# NSE2022_IMGPS_ver0.net
KiCad netlist of a schematic drawn in EAGLE
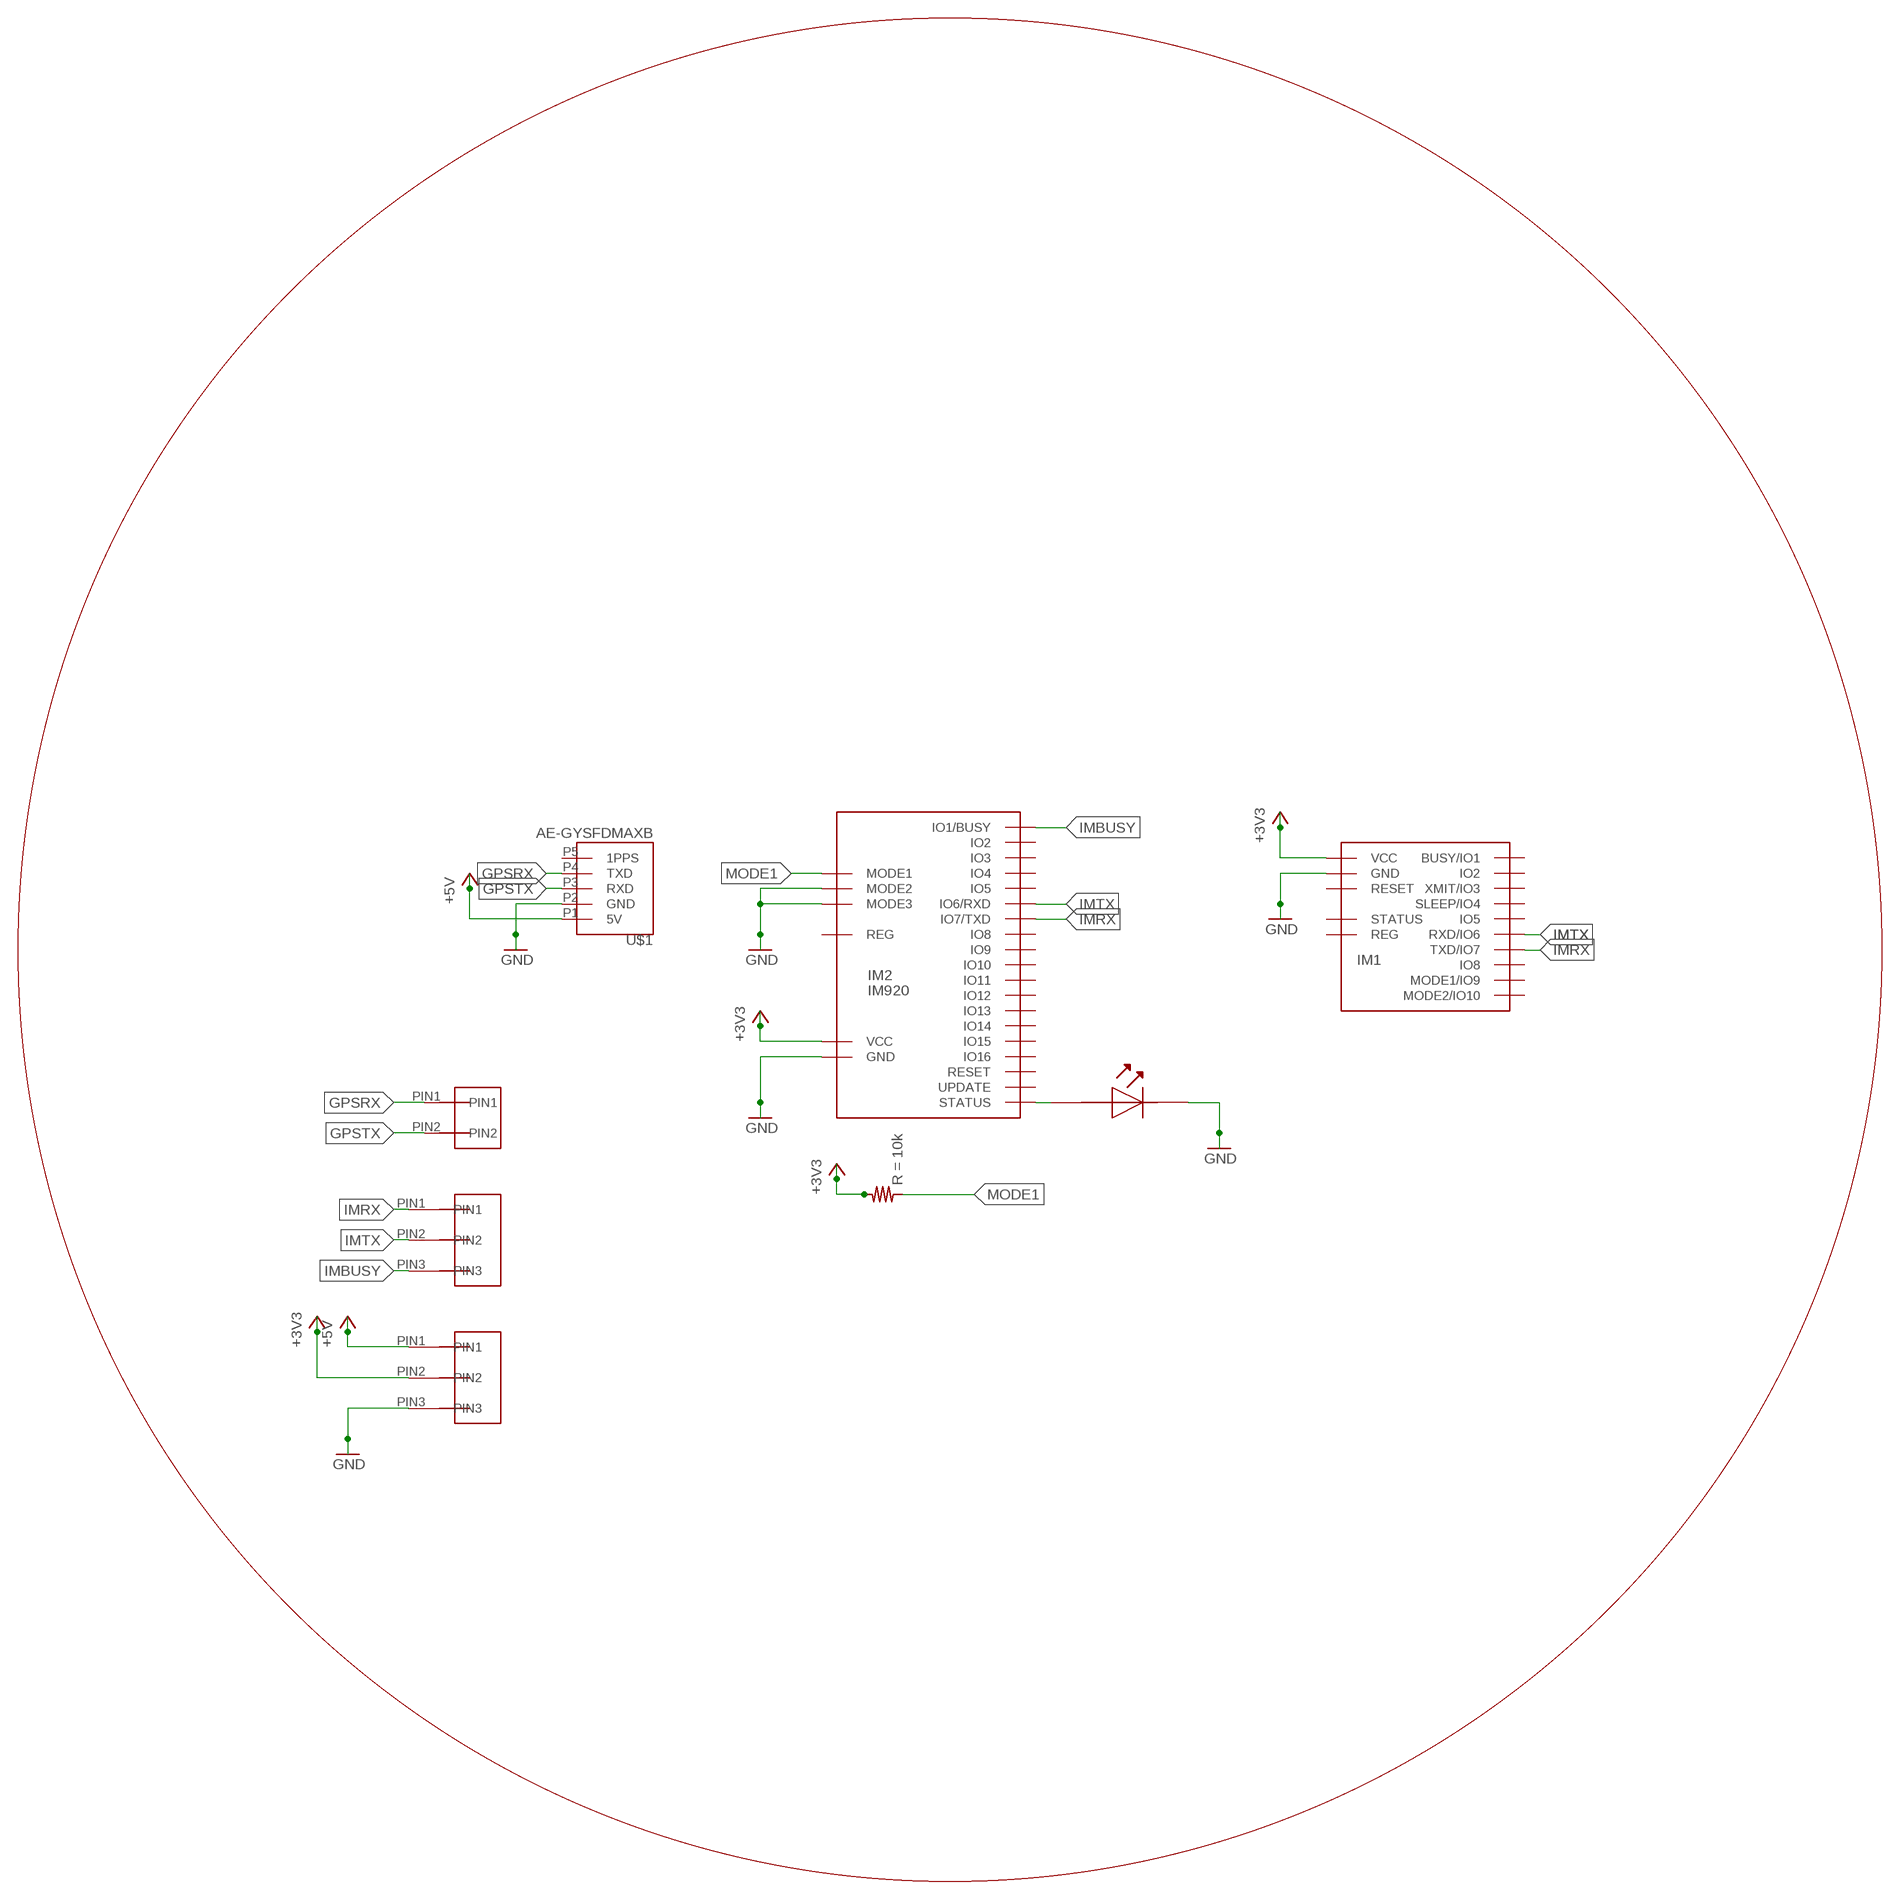
[diagram p0: schematic, sheet 1]

(export (version "E")
  (design (tool "Eeschema 10.0.6"))
  (components
    (comp (ref "IM1")
      (value "IM920C")
      (footprint "eagle-import:IM920C")
      (libsource (lib "eagle-import") (part "IM920C"))
    )
    (comp (ref "IM2")
      (value "IM920")
      (footprint "eagle-import:IM920")
      (libsource (lib "eagle-import") (part "IM920"))
    )
    (comp (ref "R4")
      (value "RESISTER")
      (footprint "eagle-import:REGISTER")
      (fields (field (name "R") "10k"))
      (libsource (lib "eagle-import") (part "RESISTER"))
    )
    (comp (ref "U$1")
      (value "AE-GYSFDMAXB")
      (footprint "eagle-import:AE-GYSFDMAXB")
      (libsource (lib "eagle-import") (part "AE-GYSFDMAXB"))
    )
    (comp (ref "U$33")
      (value "2PIN")
      (footprint "eagle-import:2PIN")
      (libsource (lib "eagle-import") (part "2PIN"))
    )
    (comp (ref "U$47")
      (value "3PIN")
      (footprint "eagle-import:3PIN")
      (libsource (lib "eagle-import") (part "3PIN"))
    )
    (comp (ref "U$48")
      (value "3PIN")
      (footprint "eagle-import:3PIN")
      (libsource (lib "eagle-import") (part "3PIN"))
    )
    (comp (ref "U$54")
      (value "LED")
      (footprint "eagle-import:LED")
      (libsource (lib "eagle-import") (part "LED"))
    )
  )
  (nets
    (net (code "1") (name "+3V3") (class "Default")
      (node (ref "IM1") (pin "$P17") (pinfunction "VCC_$P17") (pintype "bidirectional"))
      (node (ref "IM2") (pin "IO23") (pinfunction "VCC_IO23") (pintype "bidirectional"))
      (node (ref "R4") (pin "B") (pinfunction "B_B") (pintype "bidirectional"))
      (node (ref "U$48") (pin "PIN2") (pinfunction "PIN2_PIN2") (pintype "bidirectional"))
    )
    (net (code "2") (name "+5V") (class "Default")
      (node (ref "U$1") (pin "P1") (pinfunction "5V_P1") (pintype "bidirectional"))
      (node (ref "U$48") (pin "PIN1") (pinfunction "PIN1_PIN1") (pintype "bidirectional"))
    )
    (net (code "3") (name "GND") (class "Default")
      (node (ref "IM1") (pin "$P18") (pinfunction "GND_$P18") (pintype "bidirectional"))
      (node (ref "IM2") (pin "IO18") (pinfunction "MODE2_IO18") (pintype "bidirectional"))
      (node (ref "IM2") (pin "IO19") (pinfunction "MODE3_IO19") (pintype "bidirectional"))
      (node (ref "IM2") (pin "IO24") (pinfunction "GND_IO24") (pintype "bidirectional"))
      (node (ref "U$1") (pin "P2") (pinfunction "GND_P2") (pintype "bidirectional"))
      (node (ref "U$48") (pin "PIN3") (pinfunction "PIN3_PIN3") (pintype "bidirectional"))
      (node (ref "U$54") (pin "PLUS") (pinfunction "OUT_PLUS") (pintype "bidirectional"))
    )
    (net (code "4") (name "GPSRX") (class "Default")
      (node (ref "U$1") (pin "P4") (pinfunction "TXD_P4") (pintype "bidirectional"))
      (node (ref "U$33") (pin "PIN1") (pinfunction "PIN1_PIN1") (pintype "bidirectional"))
    )
    (net (code "5") (name "GPSTX") (class "Default")
      (node (ref "U$1") (pin "P3") (pinfunction "RXD_P3") (pintype "bidirectional"))
      (node (ref "U$33") (pin "PIN2") (pinfunction "PIN2_PIN2") (pintype "bidirectional"))
    )
    (net (code "6") (name "IMBUSY") (class "Default")
      (node (ref "IM2") (pin "IO1") (pinfunction "IO1/BUSY_IO1") (pintype "bidirectional"))
      (node (ref "U$47") (pin "PIN3") (pinfunction "PIN3_PIN3") (pintype "bidirectional"))
    )
    (net (code "7") (name "IMRX") (class "Default")
      (node (ref "IM1") (pin "$P7") (pinfunction "TXD/IO7_$P7") (pintype "bidirectional"))
      (node (ref "IM2") (pin "IO7") (pinfunction "IO7/TXD_IO7") (pintype "bidirectional"))
      (node (ref "U$47") (pin "PIN1") (pinfunction "PIN1_PIN1") (pintype "bidirectional"))
    )
    (net (code "8") (name "IMTX") (class "Default")
      (node (ref "IM1") (pin "$P6") (pinfunction "RXD/IO6_$P6") (pintype "bidirectional"))
      (node (ref "IM2") (pin "IO6") (pinfunction "IO6/RXD_IO6") (pintype "bidirectional"))
      (node (ref "U$47") (pin "PIN2") (pinfunction "PIN2_PIN2") (pintype "bidirectional"))
    )
    (net (code "9") (name "MODE1") (class "Default")
      (node (ref "IM2") (pin "IO17") (pinfunction "MODE1_IO17") (pintype "bidirectional"))
      (node (ref "R4") (pin "A") (pinfunction "A_A") (pintype "bidirectional"))
    )
    (net (code "10") (name "Net-(IM2-STATUS)") (class "Default")
      (node (ref "IM2") (pin "IO21") (pinfunction "STATUS_IO21") (pintype "bidirectional"))
      (node (ref "U$54") (pin "MINUS") (pinfunction "IN_MINUS") (pintype "bidirectional"))
    )
    (net (code "11") (name "unconnected-(IM1-BUSY{slash}IO1-Pad$P1)") (class "Default")
      (node (ref "IM1") (pin "$P1") (pinfunction "BUSY/IO1_$P1") (pintype "bidirectional"))
    )
    (net (code "12") (name "unconnected-(IM1-IO2-Pad$P2)") (class "Default")
      (node (ref "IM1") (pin "$P2") (pinfunction "IO2_$P2") (pintype "bidirectional"))
    )
    (net (code "13") (name "unconnected-(IM1-IO5-Pad$P5)") (class "Default")
      (node (ref "IM1") (pin "$P5") (pinfunction "IO5_$P5") (pintype "bidirectional"))
    )
    (net (code "14") (name "unconnected-(IM1-IO8-Pad$P8)") (class "Default")
      (node (ref "IM1") (pin "$P8") (pinfunction "IO8_$P8") (pintype "bidirectional"))
    )
    (net (code "15") (name "unconnected-(IM1-MODE1{slash}IO9-Pad$P9)") (class "Default")
      (node (ref "IM1") (pin "$P9") (pinfunction "MODE1/IO9_$P9") (pintype "bidirectional"))
    )
    (net (code "16") (name "unconnected-(IM1-MODE2{slash}IO10-Pad$P10)") (class "Default")
      (node (ref "IM1") (pin "$P10") (pinfunction "MODE2/IO10_$P10") (pintype "bidirectional"))
    )
    (net (code "17") (name "unconnected-(IM1-REG-Pad$P16)") (class "Default")
      (node (ref "IM1") (pin "$P16") (pinfunction "REG_$P16") (pintype "bidirectional"))
    )
    (net (code "18") (name "unconnected-(IM1-RESET-Pad$P19)") (class "Default")
      (node (ref "IM1") (pin "$P19") (pinfunction "RESET_$P19") (pintype "bidirectional"))
    )
    (net (code "19") (name "unconnected-(IM1-SLEEP{slash}IO4-Pad$P4)") (class "Default")
      (node (ref "IM1") (pin "$P4") (pinfunction "SLEEP/IO4_$P4") (pintype "bidirectional"))
    )
    (net (code "20") (name "unconnected-(IM1-STATUS-Pad$P15)") (class "Default")
      (node (ref "IM1") (pin "$P15") (pinfunction "STATUS_$P15") (pintype "bidirectional"))
    )
    (net (code "21") (name "unconnected-(IM1-XMIT{slash}IO3-Pad$P3)") (class "Default")
      (node (ref "IM1") (pin "$P3") (pinfunction "XMIT/IO3_$P3") (pintype "bidirectional"))
    )
    (net (code "22") (name "unconnected-(IM2-PadIO2)") (class "Default")
      (node (ref "IM2") (pin "IO2") (pinfunction "IO2_IO2") (pintype "bidirectional"))
    )
    (net (code "23") (name "unconnected-(IM2-PadIO3)") (class "Default")
      (node (ref "IM2") (pin "IO3") (pinfunction "IO3_IO3") (pintype "bidirectional"))
    )
    (net (code "24") (name "unconnected-(IM2-PadIO4)") (class "Default")
      (node (ref "IM2") (pin "IO4") (pinfunction "IO4_IO4") (pintype "bidirectional"))
    )
    (net (code "25") (name "unconnected-(IM2-PadIO5)") (class "Default")
      (node (ref "IM2") (pin "IO5") (pinfunction "IO5_IO5") (pintype "bidirectional"))
    )
    (net (code "26") (name "unconnected-(IM2-PadIO8)") (class "Default")
      (node (ref "IM2") (pin "IO8") (pinfunction "IO8_IO8") (pintype "bidirectional"))
    )
    (net (code "27") (name "unconnected-(IM2-PadIO9)") (class "Default")
      (node (ref "IM2") (pin "IO9") (pinfunction "IO9_IO9") (pintype "bidirectional"))
    )
    (net (code "28") (name "unconnected-(IM2-PadIO10)") (class "Default")
      (node (ref "IM2") (pin "IO10") (pinfunction "IO10_IO10") (pintype "bidirectional"))
    )
    (net (code "29") (name "unconnected-(IM2-PadIO11)") (class "Default")
      (node (ref "IM2") (pin "IO11") (pinfunction "IO11_IO11") (pintype "bidirectional"))
    )
    (net (code "30") (name "unconnected-(IM2-PadIO12)") (class "Default")
      (node (ref "IM2") (pin "IO12") (pinfunction "IO12_IO12") (pintype "bidirectional"))
    )
    (net (code "31") (name "unconnected-(IM2-PadIO13)") (class "Default")
      (node (ref "IM2") (pin "IO13") (pinfunction "IO13_IO13") (pintype "bidirectional"))
    )
    (net (code "32") (name "unconnected-(IM2-PadIO14)") (class "Default")
      (node (ref "IM2") (pin "IO14") (pinfunction "IO14_IO14") (pintype "bidirectional"))
    )
    (net (code "33") (name "unconnected-(IM2-PadIO15)") (class "Default")
      (node (ref "IM2") (pin "IO15") (pinfunction "IO15_IO15") (pintype "bidirectional"))
    )
    (net (code "34") (name "unconnected-(IM2-PadIO16)") (class "Default")
      (node (ref "IM2") (pin "IO16") (pinfunction "IO16_IO16") (pintype "bidirectional"))
    )
    (net (code "35") (name "unconnected-(IM2-REG-PadIO22)") (class "Default")
      (node (ref "IM2") (pin "IO22") (pinfunction "REG_IO22") (pintype "bidirectional"))
    )
    (net (code "36") (name "unconnected-(IM2-RESET-PadIO25)") (class "Default")
      (node (ref "IM2") (pin "IO25") (pinfunction "RESET_IO25") (pintype "bidirectional"))
    )
    (net (code "37") (name "unconnected-(IM2-UPDATE-PadIO20)") (class "Default")
      (node (ref "IM2") (pin "IO20") (pinfunction "UPDATE_IO20") (pintype "bidirectional"))
    )
    (net (code "38") (name "unconnected-(U$1-1PPS-PadP5)") (class "Default")
      (node (ref "U$1") (pin "P5") (pinfunction "1PPS_P5") (pintype "bidirectional"))
    )
  )
)
